# FOTA_Burn_Buffer.net
KiCad netlist of a schematic drawn in Altium Designer
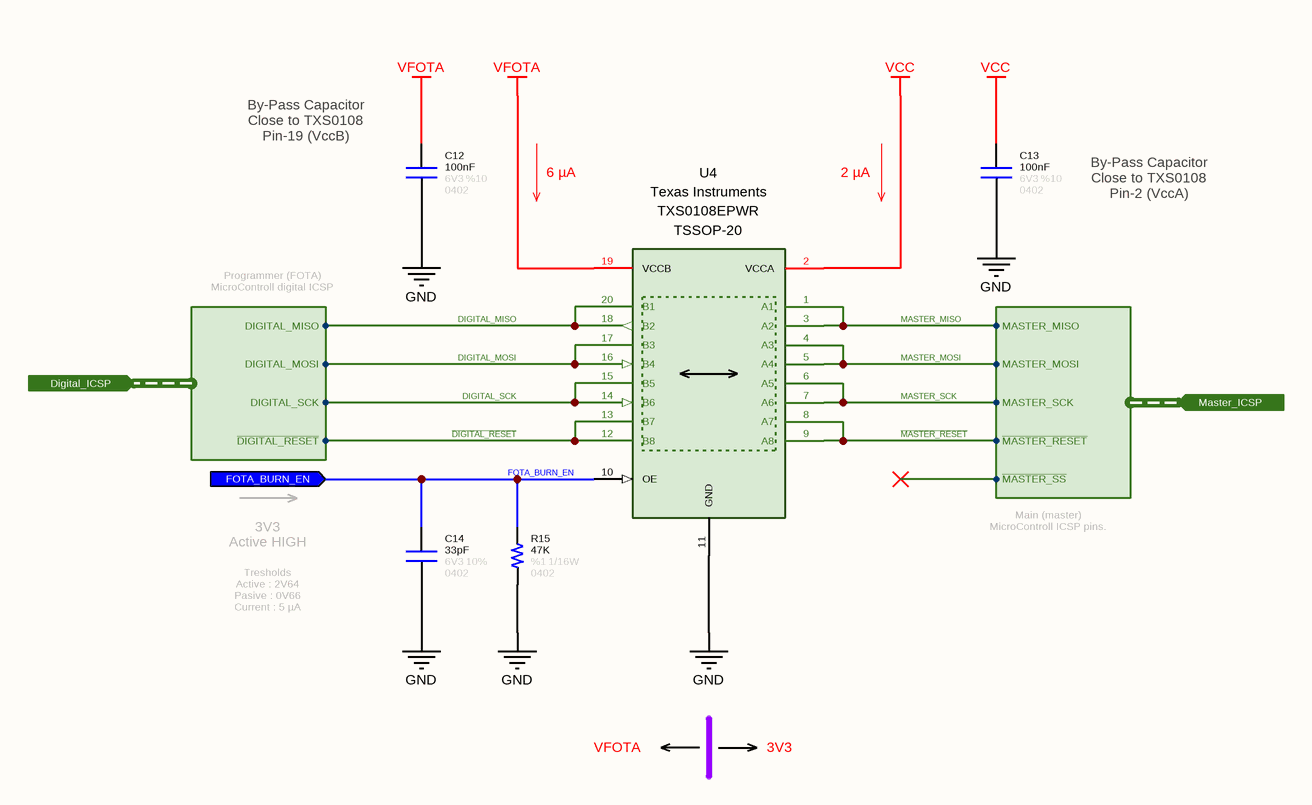
[diagram p0: FOTA Burn Buffer.SchDoc]

(export (version "E")
  (design (tool "Eeschema 10.0.6"))
  (components
    (comp (ref "C12")
      (value "100nF")
      (footprint "CAPACITOR_0402")
      (description "Capacitor - 100nF [0402-6V3] (Ceramic)")
      (fields
        (field (name "MANUFACTURER PART NUMBER") "04026D104KAT4A")
        (field (name "TOLERANCE") "%10")
        (field (name "VOLTAGE") "6V3")
        (field (name "CASE") "0402")
        (field (name "Comment") "Capacitor - 100nF [0402] (Ceramic)")
      )
      (libsource (lib "P101DA_Library") (part "Capacitor - 100nF [0402-6V3]"))
    )
    (comp (ref "C13")
      (value "100nF")
      (footprint "CAPACITOR_0402")
      (description "Capacitor - 100nF [0402-6V3] (Ceramic)")
      (fields
        (field (name "MANUFACTURER PART NUMBER") "04026D104KAT4A")
        (field (name "TOLERANCE") "%10")
        (field (name "VOLTAGE") "6V3")
        (field (name "CASE") "0402")
        (field (name "Comment") "Capacitor - 100nF [0402] (Ceramic)")
      )
      (libsource (lib "P101DA_Library") (part "Capacitor - 100nF [0402-6V3]"))
    )
    (comp (ref "C14")
      (value "33pF")
      (footprint "CAPACITOR_0402")
      (description "Capacitor - 33pF [0402] (Ceramic)")
      (fields
        (field (name "MANUFACTURER PART NUMBER") "C0402C330J9RACAUTO")
        (field (name "TOLERANCE") "10%")
        (field (name "CASE") "0402")
        (field (name "VOLTAGE") "6V3")
      )
      (libsource (lib "P101DA_Library") (part "Capacitor - 33pF [0402-6V3]"))
    )
    (comp (ref "R15")
      (value "47K")
      (footprint "RESISTOR_0402")
      (description "Thick Film Resistors - SMD 1/16 W 47 KOhm 1%")
      (fields
        (field (name "MANUFACTURER PART NUMBER") "CRCW040247K0FKED")
        (field (name "TOLERANCE") "%1")
        (field (name "CASE") "0402")
        (field (name "POWER") "1/16W")
        (field (name "Comment") "47K - 0402 - %1 - 1/16W")
      )
      (libsource (lib "P101DA_Library") (part "Resistor - 47K [0402]"))
    )
    (comp (ref "U4")
      (value "TXS0108EPWR")
      (footprint "TSSOP-20")
      (description "IC 8BIT NON-INV TRANSLTR 20TSSOP")
      (fields
        (field (name "MANUFACTURER PART NUMBER") "TXS0108EPWR")
        (field (name "MANUFACTURER NAME") "Texas Instruments")
        (field (name "CASE") "TSSOP-20")
      )
      (libsource (lib "P101DA_Library") (part "IC - TXS0108"))
    )
  )
  (nets
    (net (code "3") (name "/DIGITAL_MISO") (class "Default")
      (node (ref "U4") (pin "18") (pinfunction "B2_18") (pintype "output"))
      (node (ref "U4") (pin "20") (pinfunction "B1_20") (pintype "passive"))
    )
    (net (code "4") (name "/DIGITAL_MOSI") (class "Default")
      (node (ref "U4") (pin "16") (pinfunction "B4_16") (pintype "input"))
      (node (ref "U4") (pin "17") (pinfunction "B3_17") (pintype "passive"))
    )
    (net (code "5") (name "/DIGITAL_SCK") (class "Default")
      (node (ref "U4") (pin "14") (pinfunction "B6_14") (pintype "input"))
      (node (ref "U4") (pin "15") (pinfunction "B5_15") (pintype "passive"))
    )
    (net (code "6") (name "/FOTA_BURN_EN") (class "Default")
      (node (ref "C14") (pin "2") (pinfunction "2_2") (pintype "passive"))
      (node (ref "R15") (pin "2") (pinfunction "2_2") (pintype "passive"))
      (node (ref "U4") (pin "10") (pinfunction "OE_10") (pintype "input"))
    )
    (net (code "7") (name "/MASTER_MISO") (class "Default")
      (node (ref "U4") (pin "1") (pinfunction "A1_1") (pintype "passive"))
      (node (ref "U4") (pin "3") (pinfunction "A2_3") (pintype "passive"))
    )
    (net (code "8") (name "/MASTER_MOSI") (class "Default")
      (node (ref "U4") (pin "4") (pinfunction "A3_4") (pintype "passive"))
      (node (ref "U4") (pin "5") (pinfunction "A4_5") (pintype "passive"))
    )
    (net (code "9") (name "/MASTER_SCK") (class "Default")
      (node (ref "U4") (pin "6") (pinfunction "A5_6") (pintype "passive"))
      (node (ref "U4") (pin "7") (pinfunction "A6_7") (pintype "passive"))
    )
    (net (code "12") (name "/~{DIGITAL_RESET}") (class "Default")
      (node (ref "U4") (pin "12") (pinfunction "B8_12") (pintype "passive"))
      (node (ref "U4") (pin "13") (pinfunction "B7_13") (pintype "passive"))
    )
    (net (code "13") (name "/~{MASTER_RESET}") (class "Default")
      (node (ref "U4") (pin "8") (pinfunction "A7_8") (pintype "passive"))
      (node (ref "U4") (pin "9") (pinfunction "A8_9") (pintype "passive"))
    )
    (net (code "14") (name "GND") (class "Default")
      (node (ref "C12") (pin "1") (pinfunction "1_1") (pintype "passive"))
      (node (ref "C13") (pin "1") (pinfunction "1_1") (pintype "passive"))
      (node (ref "C14") (pin "1") (pinfunction "1_1") (pintype "passive"))
      (node (ref "R15") (pin "1") (pinfunction "1_1") (pintype "passive"))
      (node (ref "U4") (pin "11") (pinfunction "GND_11") (pintype "passive"))
    )
    (net (code "15") (name "VCC") (class "Default")
      (node (ref "C13") (pin "2") (pinfunction "2_2") (pintype "passive"))
      (node (ref "U4") (pin "2") (pinfunction "VCCA_2") (pintype "power_in"))
    )
    (net (code "16") (name "VFOTA") (class "Default")
      (node (ref "C12") (pin "2") (pinfunction "2_2") (pintype "passive"))
      (node (ref "U4") (pin "19") (pinfunction "VCCB_19") (pintype "power_in"))
    )
  )
)
